# Shruthi-Analog-CS80-SVF-v01_xml.net
KiCad netlist of a schematic drawn in EAGLE
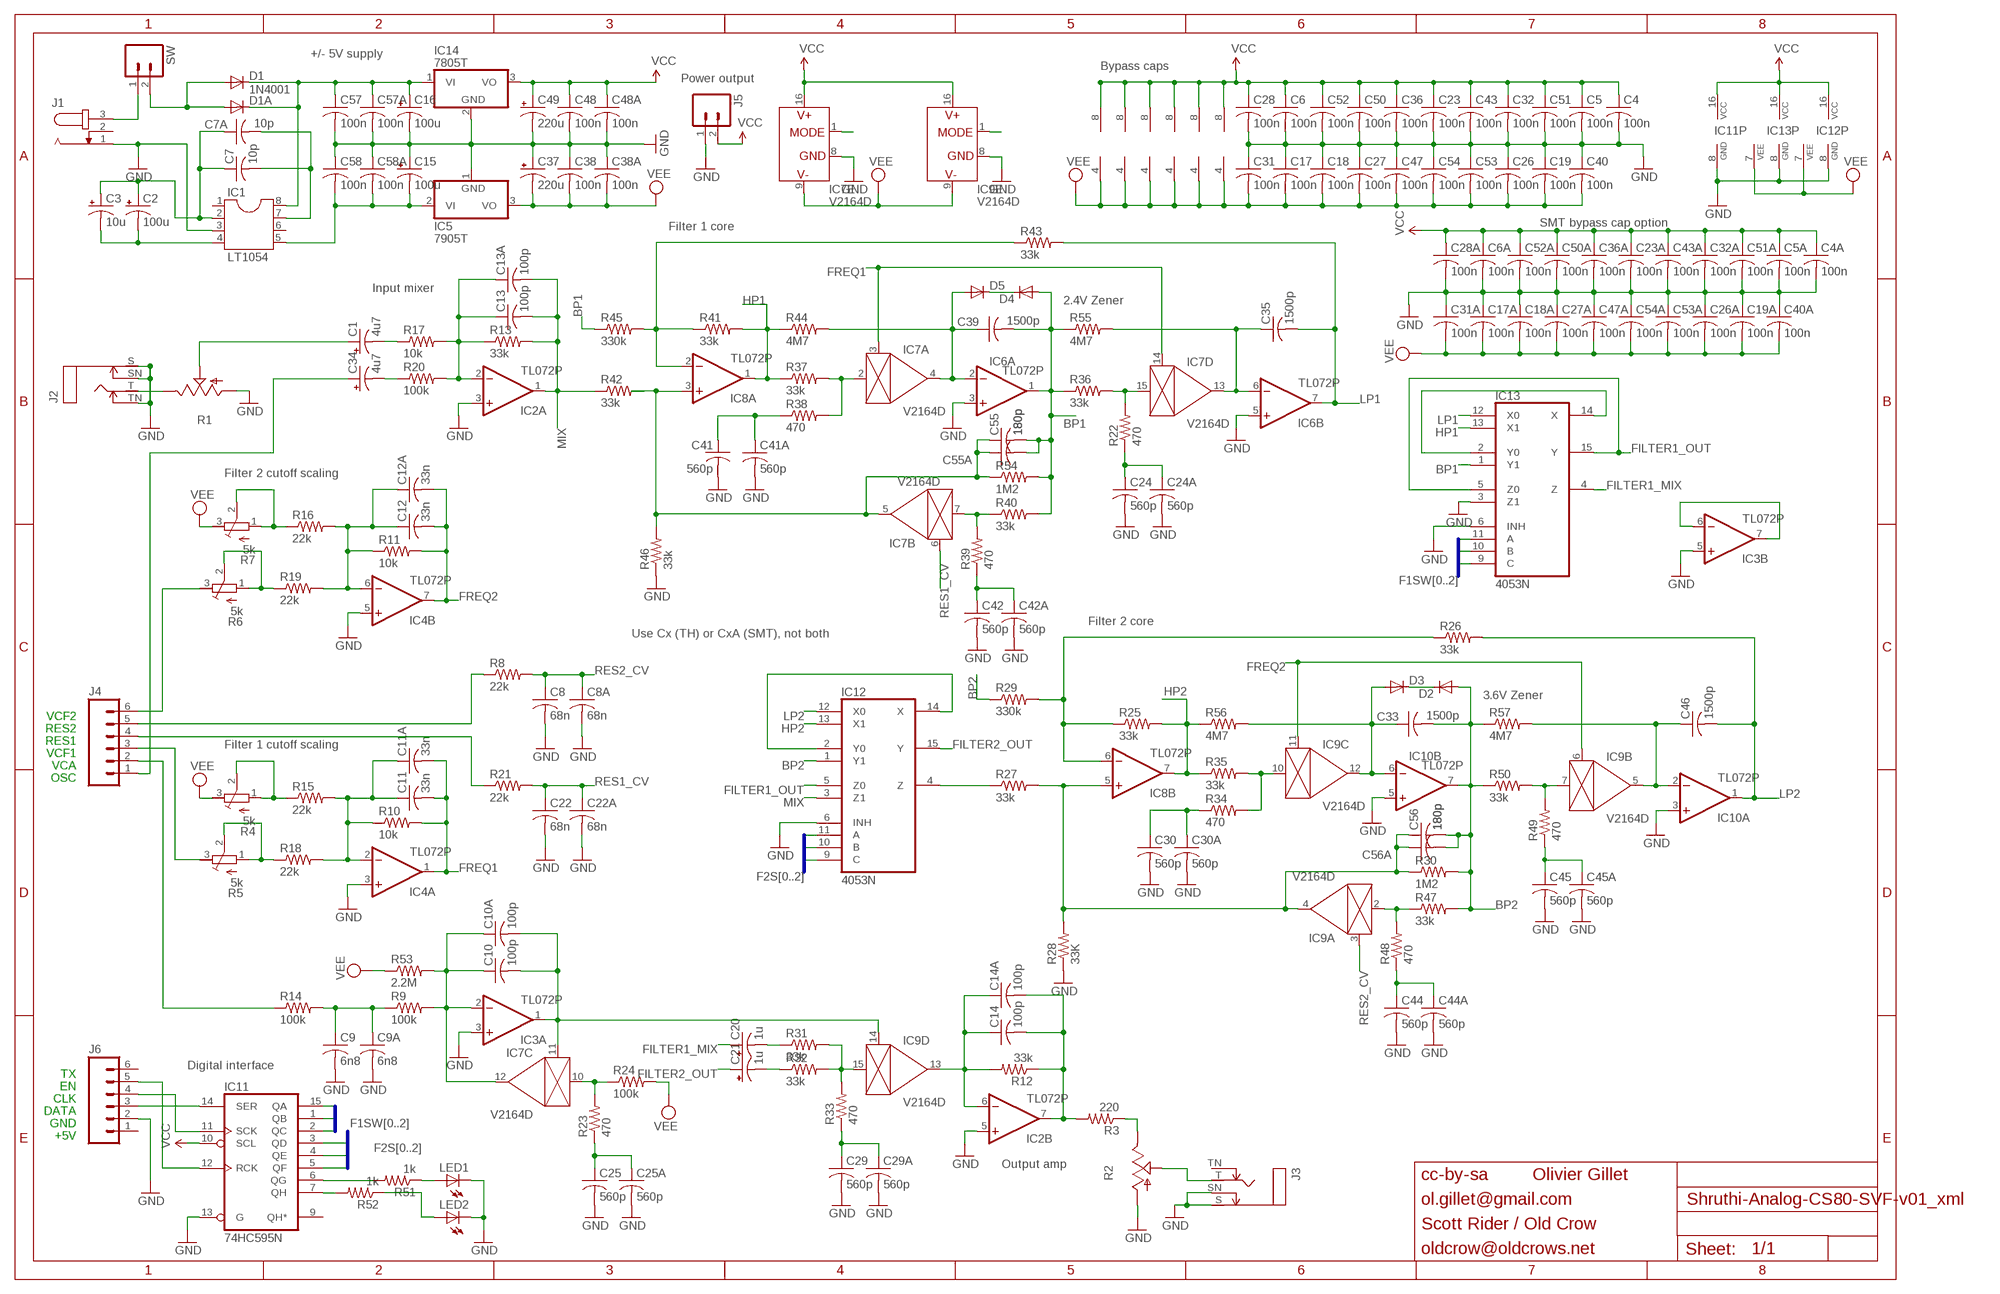
[diagram p0: schematic, sheet 1]

(export (version "E")
  (design (tool "Eeschema 10.0.6"))
  (components
    (comp (ref "C1")
      (value "4u7")
      (footprint "eagle-import:E2,5-6")
      (libsource (lib "eagle-import") (part "CPOL-USE2.5-6"))
    )
    (comp (ref "C2")
      (value "100u")
      (footprint "eagle-import:E2,5-6")
      (libsource (lib "eagle-import") (part "CPOL-USE2.5-6"))
    )
    (comp (ref "C3")
      (value "10u")
      (footprint "eagle-import:E2,5-5")
      (libsource (lib "eagle-import") (part "CPOL-USE2.5-5"))
    )
    (comp (ref "C4")
      (value "100n")
      (footprint "eagle-import:C050-025X075")
      (libsource (lib "eagle-import") (part "C-US050-025X075"))
    )
    (comp (ref "C4A")
      (value "100n")
      (footprint "eagle-import:C0805K")
      (libsource (lib "eagle-import") (part "C-USC0805K"))
    )
    (comp (ref "C5")
      (value "100n")
      (footprint "eagle-import:C050-025X075")
      (libsource (lib "eagle-import") (part "C-US050-025X075"))
    )
    (comp (ref "C5A")
      (value "100n")
      (footprint "eagle-import:C0805K")
      (libsource (lib "eagle-import") (part "C-USC0805K"))
    )
    (comp (ref "C6")
      (value "100n")
      (footprint "eagle-import:C050-025X075")
      (libsource (lib "eagle-import") (part "C-US050-025X075"))
    )
    (comp (ref "C6A")
      (value "100n")
      (footprint "eagle-import:C0805K")
      (libsource (lib "eagle-import") (part "C-USC0805K"))
    )
    (comp (ref "C7")
      (value "10p")
      (footprint "eagle-import:C050-025X075")
      (libsource (lib "eagle-import") (part "C-US050-025X075"))
    )
    (comp (ref "C7A")
      (value "10p")
      (footprint "eagle-import:C0805K")
      (libsource (lib "eagle-import") (part "C-USC0805K"))
    )
    (comp (ref "C8")
      (value "68n")
      (footprint "eagle-import:C050-025X075")
      (libsource (lib "eagle-import") (part "C-US050-025X075"))
    )
    (comp (ref "C8A")
      (value "68n")
      (footprint "eagle-import:C0805K")
      (libsource (lib "eagle-import") (part "C-USC0805K"))
    )
    (comp (ref "C9")
      (value "6n8")
      (footprint "eagle-import:C050-025X075")
      (libsource (lib "eagle-import") (part "C-US050-025X075"))
    )
    (comp (ref "C9A")
      (value "6n8")
      (footprint "eagle-import:C0805K")
      (libsource (lib "eagle-import") (part "C-USC0805K"))
    )
    (comp (ref "C10")
      (value "100p")
      (footprint "eagle-import:C050-025X075")
      (libsource (lib "eagle-import") (part "C-US050-025X075"))
    )
    (comp (ref "C10A")
      (value "100p")
      (footprint "eagle-import:C0805K")
      (libsource (lib "eagle-import") (part "C-USC0805K"))
    )
    (comp (ref "C11")
      (value "33n")
      (footprint "eagle-import:C050-025X075")
      (libsource (lib "eagle-import") (part "C-US050-025X075"))
    )
    (comp (ref "C11A")
      (value "33n")
      (footprint "eagle-import:C0805K")
      (libsource (lib "eagle-import") (part "C-USC0805K"))
    )
    (comp (ref "C12")
      (value "33n")
      (footprint "eagle-import:C050-025X075")
      (libsource (lib "eagle-import") (part "C-US050-025X075"))
    )
    (comp (ref "C12A")
      (value "33n")
      (footprint "eagle-import:C0805K")
      (libsource (lib "eagle-import") (part "C-USC0805K"))
    )
    (comp (ref "C13")
      (value "100p")
      (footprint "eagle-import:C050-025X075")
      (libsource (lib "eagle-import") (part "C-US050-025X075"))
    )
    (comp (ref "C13A")
      (value "100p")
      (footprint "eagle-import:C0805K")
      (libsource (lib "eagle-import") (part "C-USC0805K"))
    )
    (comp (ref "C14")
      (value "100p")
      (footprint "eagle-import:C050-025X075")
      (libsource (lib "eagle-import") (part "C-US050-025X075"))
    )
    (comp (ref "C14A")
      (value "100p")
      (footprint "eagle-import:C0805K")
      (libsource (lib "eagle-import") (part "C-USC0805K"))
    )
    (comp (ref "C15")
      (value "100u")
      (footprint "eagle-import:E2,5-7")
      (libsource (lib "eagle-import") (part "CPOL-USE2.5-7"))
    )
    (comp (ref "C16")
      (value "100u")
      (footprint "eagle-import:E2,5-7")
      (libsource (lib "eagle-import") (part "CPOL-USE2.5-7"))
    )
    (comp (ref "C17")
      (value "100n")
      (footprint "eagle-import:C050-025X075")
      (libsource (lib "eagle-import") (part "C-US050-025X075"))
    )
    (comp (ref "C17A")
      (value "100n")
      (footprint "eagle-import:C0805K")
      (libsource (lib "eagle-import") (part "C-USC0805K"))
    )
    (comp (ref "C18")
      (value "100n")
      (footprint "eagle-import:C050-025X075")
      (libsource (lib "eagle-import") (part "C-US050-025X075"))
    )
    (comp (ref "C18A")
      (value "100n")
      (footprint "eagle-import:C0805K")
      (libsource (lib "eagle-import") (part "C-USC0805K"))
    )
    (comp (ref "C19")
      (value "100n")
      (footprint "eagle-import:C050-025X075")
      (libsource (lib "eagle-import") (part "C-US050-025X075"))
    )
    (comp (ref "C19A")
      (value "100n")
      (footprint "eagle-import:C0805K")
      (libsource (lib "eagle-import") (part "C-USC0805K"))
    )
    (comp (ref "C20")
      (value "1u")
      (footprint "eagle-import:E2-5")
      (libsource (lib "eagle-import") (part "CPOL-USE2-5"))
    )
    (comp (ref "C21")
      (value "1u")
      (footprint "eagle-import:E2-5")
      (libsource (lib "eagle-import") (part "CPOL-USE2-5"))
    )
    (comp (ref "C22")
      (value "68n")
      (footprint "eagle-import:C050-025X075")
      (libsource (lib "eagle-import") (part "C-US050-025X075"))
    )
    (comp (ref "C22A")
      (value "68n")
      (footprint "eagle-import:C0805K")
      (libsource (lib "eagle-import") (part "C-USC0805K"))
    )
    (comp (ref "C23")
      (value "100n")
      (footprint "eagle-import:C050-025X075")
      (libsource (lib "eagle-import") (part "C-US050-025X075"))
    )
    (comp (ref "C23A")
      (value "100n")
      (footprint "eagle-import:C0805K")
      (libsource (lib "eagle-import") (part "C-USC0805K"))
    )
    (comp (ref "C24")
      (value "560p")
      (footprint "eagle-import:C050-025X075")
      (libsource (lib "eagle-import") (part "C-US050-025X075"))
    )
    (comp (ref "C24A")
      (value "560p")
      (footprint "eagle-import:C0805K")
      (libsource (lib "eagle-import") (part "C-USC0805K"))
    )
    (comp (ref "C25")
      (value "560p")
      (footprint "eagle-import:C050-025X075")
      (libsource (lib "eagle-import") (part "C-US050-025X075"))
    )
    (comp (ref "C25A")
      (value "560p")
      (footprint "eagle-import:C0805K")
      (libsource (lib "eagle-import") (part "C-USC0805K"))
    )
    (comp (ref "C26")
      (value "100n")
      (footprint "eagle-import:C050-025X075")
      (libsource (lib "eagle-import") (part "C-US050-025X075"))
    )
    (comp (ref "C26A")
      (value "100n")
      (footprint "eagle-import:C0805K")
      (libsource (lib "eagle-import") (part "C-USC0805K"))
    )
    (comp (ref "C27")
      (value "100n")
      (footprint "eagle-import:C050-025X075")
      (libsource (lib "eagle-import") (part "C-US050-025X075"))
    )
    (comp (ref "C27A")
      (value "100n")
      (footprint "eagle-import:C0805K")
      (libsource (lib "eagle-import") (part "C-USC0805K"))
    )
    (comp (ref "C28")
      (value "100n")
      (footprint "eagle-import:C050-025X075")
      (libsource (lib "eagle-import") (part "C-US050-025X075"))
    )
    (comp (ref "C28A")
      (value "100n")
      (footprint "eagle-import:C0805K")
      (libsource (lib "eagle-import") (part "C-USC0805K"))
    )
    (comp (ref "C29")
      (value "560p")
      (footprint "eagle-import:C050-025X075")
      (libsource (lib "eagle-import") (part "C-US050-025X075"))
    )
    (comp (ref "C29A")
      (value "560p")
      (footprint "eagle-import:C0805K")
      (libsource (lib "eagle-import") (part "C-USC0805K"))
    )
    (comp (ref "C30")
      (value "560p")
      (footprint "eagle-import:C050-025X075")
      (libsource (lib "eagle-import") (part "C-US050-025X075"))
    )
    (comp (ref "C30A")
      (value "560p")
      (footprint "eagle-import:C0805K")
      (libsource (lib "eagle-import") (part "C-USC0805K"))
    )
    (comp (ref "C31")
      (value "100n")
      (footprint "eagle-import:C050-025X075")
      (libsource (lib "eagle-import") (part "C-US050-025X075"))
    )
    (comp (ref "C31A")
      (value "100n")
      (footprint "eagle-import:C0805K")
      (libsource (lib "eagle-import") (part "C-USC0805K"))
    )
    (comp (ref "C32")
      (value "100n")
      (footprint "eagle-import:C050-025X075")
      (libsource (lib "eagle-import") (part "C-US050-025X075"))
    )
    (comp (ref "C32A")
      (value "100n")
      (footprint "eagle-import:C0805K")
      (libsource (lib "eagle-import") (part "C-USC0805K"))
    )
    (comp (ref "C33")
      (value "1500p")
      (footprint "eagle-import:C025-025X050")
      (libsource (lib "eagle-import") (part "C-US025-025X050"))
    )
    (comp (ref "C34")
      (value "4u7")
      (footprint "eagle-import:E2,5-6")
      (libsource (lib "eagle-import") (part "CPOL-USE2.5-6"))
    )
    (comp (ref "C35")
      (value "1500p")
      (footprint "eagle-import:C025-025X050")
      (libsource (lib "eagle-import") (part "C-US025-025X050"))
    )
    (comp (ref "C36")
      (value "100n")
      (footprint "eagle-import:C050-025X075")
      (libsource (lib "eagle-import") (part "C-US050-025X075"))
    )
    (comp (ref "C36A")
      (value "100n")
      (footprint "eagle-import:C0805K")
      (libsource (lib "eagle-import") (part "C-USC0805K"))
    )
    (comp (ref "C37")
      (value "220u")
      (footprint "eagle-import:E3,5-8")
      (libsource (lib "eagle-import") (part "CPOL-USE3.5-8"))
    )
    (comp (ref "C38")
      (value "100n")
      (footprint "eagle-import:C050-025X075")
      (libsource (lib "eagle-import") (part "C-US050-025X075"))
    )
    (comp (ref "C38A")
      (value "100n")
      (footprint "eagle-import:C0805K")
      (libsource (lib "eagle-import") (part "C-USC0805K"))
    )
    (comp (ref "C39")
      (value "1500p")
      (footprint "eagle-import:C025-025X050")
      (libsource (lib "eagle-import") (part "C-US025-025X050"))
    )
    (comp (ref "C40")
      (value "100n")
      (footprint "eagle-import:C050-025X075")
      (libsource (lib "eagle-import") (part "C-US050-025X075"))
    )
    (comp (ref "C40A")
      (value "100n")
      (footprint "eagle-import:C0805K")
      (libsource (lib "eagle-import") (part "C-USC0805K"))
    )
    (comp (ref "C41")
      (value "560p")
      (footprint "eagle-import:C050-025X075")
      (libsource (lib "eagle-import") (part "C-US050-025X075"))
    )
    (comp (ref "C41A")
      (value "560p")
      (footprint "eagle-import:C0805K")
      (libsource (lib "eagle-import") (part "C-USC0805K"))
    )
    (comp (ref "C42")
      (value "560p")
      (footprint "eagle-import:C050-025X075")
      (libsource (lib "eagle-import") (part "C-US050-025X075"))
    )
    (comp (ref "C42A")
      (value "560p")
      (footprint "eagle-import:C0805K")
      (libsource (lib "eagle-import") (part "C-USC0805K"))
    )
    (comp (ref "C43")
      (value "100n")
      (footprint "eagle-import:C050-025X075")
      (libsource (lib "eagle-import") (part "C-US050-025X075"))
    )
    (comp (ref "C43A")
      (value "100n")
      (footprint "eagle-import:C0805K")
      (libsource (lib "eagle-import") (part "C-USC0805K"))
    )
    (comp (ref "C44")
      (value "560p")
      (footprint "eagle-import:C050-025X075")
      (libsource (lib "eagle-import") (part "C-US050-025X075"))
    )
    (comp (ref "C44A")
      (value "560p")
      (footprint "eagle-import:C0805K")
      (libsource (lib "eagle-import") (part "C-USC0805K"))
    )
    (comp (ref "C45")
      (value "560p")
      (footprint "eagle-import:C050-025X075")
      (libsource (lib "eagle-import") (part "C-US050-025X075"))
    )
    (comp (ref "C45A")
      (value "560p")
      (footprint "eagle-import:C0805K")
      (libsource (lib "eagle-import") (part "C-USC0805K"))
    )
    (comp (ref "C46")
      (value "1500p")
      (footprint "eagle-import:C025-025X050")
      (libsource (lib "eagle-import") (part "C-US025-025X050"))
    )
    (comp (ref "C47")
      (value "100n")
      (footprint "eagle-import:C050-025X075")
      (libsource (lib "eagle-import") (part "C-US050-025X075"))
    )
    (comp (ref "C47A")
      (value "100n")
      (footprint "eagle-import:C0805K")
      (libsource (lib "eagle-import") (part "C-USC0805K"))
    )
    (comp (ref "C48")
      (value "100n")
      (footprint "eagle-import:C050-025X075")
      (libsource (lib "eagle-import") (part "C-US050-025X075"))
    )
    (comp (ref "C48A")
      (value "100n")
      (footprint "eagle-import:C0805K")
      (libsource (lib "eagle-import") (part "C-USC0805K"))
    )
    (comp (ref "C49")
      (value "220u")
      (footprint "eagle-import:E3,5-8")
      (libsource (lib "eagle-import") (part "CPOL-USE3.5-8"))
    )
    (comp (ref "C50")
      (value "100n")
      (footprint "eagle-import:C050-025X075")
      (libsource (lib "eagle-import") (part "C-US050-025X075"))
    )
    (comp (ref "C50A")
      (value "100n")
      (footprint "eagle-import:C0805K")
      (libsource (lib "eagle-import") (part "C-USC0805K"))
    )
    (comp (ref "C51")
      (value "100n")
      (footprint "eagle-import:C050-025X075")
      (libsource (lib "eagle-import") (part "C-US050-025X075"))
    )
    (comp (ref "C51A")
      (value "100n")
      (footprint "eagle-import:C0805K")
      (libsource (lib "eagle-import") (part "C-USC0805K"))
    )
    (comp (ref "C52")
      (value "100n")
      (footprint "eagle-import:C050-025X075")
      (libsource (lib "eagle-import") (part "C-US050-025X075"))
    )
    (comp (ref "C52A")
      (value "100n")
      (footprint "eagle-import:C0805K")
      (libsource (lib "eagle-import") (part "C-USC0805K"))
    )
    (comp (ref "C53")
      (value "100n")
      (footprint "eagle-import:C025-025X050")
      (libsource (lib "eagle-import") (part "C-US025-025X050"))
    )
    (comp (ref "C53A")
      (value "100n")
      (footprint "eagle-import:C0805K")
      (libsource (lib "eagle-import") (part "C-USC0805K"))
    )
    (comp (ref "C54")
      (value "100n")
      (footprint "eagle-import:C050-025X075")
      (libsource (lib "eagle-import") (part "C-US050-025X075"))
    )
    (comp (ref "C54A")
      (value "100n")
      (footprint "eagle-import:C0805K")
      (libsource (lib "eagle-import") (part "C-USC0805K"))
    )
    (comp (ref "C55")
      (value "180p")
      (footprint "eagle-import:C050-025X075")
      (libsource (lib "eagle-import") (part "C-US050-025X075"))
    )
    (comp (ref "C55A")
      (value "180p")
      (footprint "eagle-import:C0805K")
      (libsource (lib "eagle-import") (part "C-USC0805K"))
    )
    (comp (ref "C56")
      (value "180p")
      (footprint "eagle-import:C050-025X075")
      (libsource (lib "eagle-import") (part "C-US050-025X075"))
    )
    (comp (ref "C56A")
      (value "180p")
      (footprint "eagle-import:C0805K")
      (libsource (lib "eagle-import") (part "C-USC0805K"))
    )
    (comp (ref "C57")
      (value "100n")
      (footprint "eagle-import:C050-025X075")
      (libsource (lib "eagle-import") (part "C-US050-025X075"))
    )
    (comp (ref "C57A")
      (value "100n")
      (footprint "eagle-import:C0805K")
      (libsource (lib "eagle-import") (part "C-USC0805K"))
    )
    (comp (ref "C58")
      (value "100n")
      (footprint "eagle-import:C050-025X075")
      (libsource (lib "eagle-import") (part "C-US050-025X075"))
    )
    (comp (ref "C58A")
      (value "100n")
      (footprint "eagle-import:C0805K")
      (libsource (lib "eagle-import") (part "C-USC0805K"))
    )
    (comp (ref "D1")
      (value "1N4001")
      (footprint "eagle-import:DO41-10")
      (libsource (lib "eagle-import") (part "1N4004"))
    )
    (comp (ref "D1A")
      (value "DIODE-SMB")
      (footprint "eagle-import:SMB")
      (libsource (lib "eagle-import") (part "DIODE-SMB"))
    )
    (comp (ref "D2")
      (value "DIODE-D-5")
      (footprint "eagle-import:D-5")
      (libsource (lib "eagle-import") (part "DIODE-D-5"))
    )
    (comp (ref "D3")
      (value "DIODE-D-5")
      (footprint "eagle-import:D-5")
      (libsource (lib "eagle-import") (part "DIODE-D-5"))
    )
    (comp (ref "D4")
      (value "DIODE-D-5")
      (footprint "eagle-import:D-5")
      (libsource (lib "eagle-import") (part "DIODE-D-5"))
    )
    (comp (ref "D5")
      (value "DIODE-D-5")
      (footprint "eagle-import:D-5")
      (libsource (lib "eagle-import") (part "DIODE-D-5"))
    )
    (comp (ref "IC1")
      (value "LT1054")
      (footprint "eagle-import:DIL08")
      (libsource (lib "eagle-import") (part "DIL8"))
    )
    (comp (ref "IC2")
      (value "TL072P")
      (footprint "eagle-import:DIL08")
      (libsource (lib "eagle-import") (part "TL072P"))
    )
    (comp (ref "IC3")
      (value "TL072P")
      (footprint "eagle-import:DIL08")
      (libsource (lib "eagle-import") (part "TL072P"))
    )
    (comp (ref "IC4")
      (value "TL072P")
      (footprint "eagle-import:DIL08")
      (libsource (lib "eagle-import") (part "TL072P"))
    )
    (comp (ref "IC5")
      (value "7905T")
      (footprint "eagle-import:TO220H")
      (libsource (lib "eagle-import") (part "79T05"))
    )
    (comp (ref "IC6")
      (value "TL072P")
      (footprint "eagle-import:DIL08")
      (libsource (lib "eagle-import") (part "TL072P"))
    )
    (comp (ref "IC7")
      (value "V2164D")
      (footprint "eagle-import:DIL16")
      (libsource (lib "eagle-import") (part "SSM2164P"))
    )
    (comp (ref "IC8")
      (value "TL072P")
      (footprint "eagle-import:DIL08")
      (libsource (lib "eagle-import") (part "TL072P"))
    )
    (comp (ref "IC9")
      (value "V2164D")
      (footprint "eagle-import:DIL16")
      (libsource (lib "eagle-import") (part "SSM2164P"))
    )
    (comp (ref "IC10")
      (value "TL072P")
      (footprint "eagle-import:DIL08")
      (libsource (lib "eagle-import") (part "TL072P"))
    )
    (comp (ref "IC11")
      (value "74HC595N")
      (footprint "eagle-import:DIL16")
      (libsource (lib "eagle-import") (part "74595NHC"))
    )
    (comp (ref "IC12")
      (value "4053N")
      (footprint "eagle-import:DIL16")
      (libsource (lib "eagle-import") (part "4053N"))
    )
    (comp (ref "IC13")
      (value "4053N")
      (footprint "eagle-import:DIL16")
      (libsource (lib "eagle-import") (part "4053N"))
    )
    (comp (ref "IC14")
      (value "7805T")
      (footprint "eagle-import:TO220H")
      (libsource (lib "eagle-import") (part "78T05"))
    )
    (comp (ref "J1")
      (value "JACK-PLUG2")
      (footprint "eagle-import:SPC4078_BIG_HOLES")
      (libsource (lib "eagle-import") (part "JACK-PLUG2"))
    )
    (comp (ref "J2")
      (value "MONOSWS")
      (footprint "eagle-import:NMJ4HC-S")
      (libsource (lib "eagle-import") (part "MONOSWS"))
    )
    (comp (ref "J3")
      (value "MONOSWS")
      (footprint "eagle-import:NMJ4HC-S")
      (libsource (lib "eagle-import") (part "MONOSWS"))
    )
    (comp (ref "J4")
      (value "M06SIP")
      (footprint "eagle-import:1X06")
      (libsource (lib "eagle-import") (part "M06SIP"))
    )
    (comp (ref "J5")
      (value "M02PTH")
      (footprint "eagle-import:1X02")
      (libsource (lib "eagle-import") (part "M02PTH"))
    )
    (comp (ref "J6")
      (value "M06SIP")
      (footprint "eagle-import:1X06")
      (libsource (lib "eagle-import") (part "M06SIP"))
    )
    (comp (ref "LED1")
      (value "LEDCHIP-LED0603")
      (footprint "eagle-import:CHIP-LED0603")
      (libsource (lib "eagle-import") (part "LEDCHIP-LED0603"))
    )
    (comp (ref "LED2")
      (value "LEDCHIP-LED0603")
      (footprint "eagle-import:CHIP-LED0603")
      (libsource (lib "eagle-import") (part "LEDCHIP-LED0603"))
    )
    (comp (ref "R1")
      (value "POT_USCABLED")
      (footprint "eagle-import:CABLE_POT_6MM")
      (libsource (lib "eagle-import") (part "POT_USCABLED"))
    )
    (comp (ref "R2")
      (value "POT_USCABLED")
      (footprint "eagle-import:CABLE_POT_6MM")
      (libsource (lib "eagle-import") (part "POT_USCABLED"))
    )
    (comp (ref "R3")
      (value "220")
      (footprint "eagle-import:0204_7")
      (libsource (lib "eagle-import") (part "R-US_0204/7"))
    )
    (comp (ref "R4")
      (value "5k")
      (footprint "eagle-import:RTRIM3296X")
      (libsource (lib "eagle-import") (part "R-TRIMM3296X"))
    )
    (comp (ref "R5")
      (value "5k")
      (footprint "eagle-import:RTRIM3296X")
      (libsource (lib "eagle-import") (part "R-TRIMM3296X"))
    )
    (comp (ref "R6")
      (value "5k")
      (footprint "eagle-import:RTRIM3296X")
      (libsource (lib "eagle-import") (part "R-TRIMM3296X"))
    )
    (comp (ref "R7")
      (value "5k")
      (footprint "eagle-import:RTRIM3296X")
      (libsource (lib "eagle-import") (part "R-TRIMM3296X"))
    )
    (comp (ref "R8")
      (value "22k")
      (footprint "eagle-import:0204_7")
      (libsource (lib "eagle-import") (part "R-US_0204/7"))
    )
    (comp (ref "R9")
      (value "100k")
      (footprint "eagle-import:0204_7")
      (libsource (lib "eagle-import") (part "R-US_0204/7"))
    )
    (comp (ref "R10")
      (value "10k")
      (footprint "eagle-import:0204_7")
      (libsource (lib "eagle-import") (part "R-US_0204/7"))
    )
    (comp (ref "R11")
      (value "10k")
      (footprint "eagle-import:0204_7")
      (libsource (lib "eagle-import") (part "R-US_0204/7"))
    )
    (comp (ref "R12")
      (value "33k")
      (footprint "eagle-import:0204_7")
      (libsource (lib "eagle-import") (part "R-US_0204/7"))
    )
    (comp (ref "R13")
      (value "33k")
      (footprint "eagle-import:0204_7")
      (libsource (lib "eagle-import") (part "R-US_0204/7"))
    )
    (comp (ref "R14")
      (value "100k")
      (footprint "eagle-import:0204_7")
      (libsource (lib "eagle-import") (part "R-US_0204/7"))
    )
    (comp (ref "R15")
      (value "22k")
      (footprint "eagle-import:0204_7")
      (libsource (lib "eagle-import") (part "R-US_0204/7"))
    )
    (comp (ref "R16")
      (value "22k")
      (footprint "eagle-import:0204_7")
      (libsource (lib "eagle-import") (part "R-US_0204/7"))
    )
    (comp (ref "R17")
      (value "10k")
      (footprint "eagle-import:0204_7")
      (libsource (lib "eagle-import") (part "R-US_0204/7"))
    )
    (comp (ref "R18")
      (value "22k")
      (footprint "eagle-import:0204_7")
      (libsource (lib "eagle-import") (part "R-US_0204/7"))
    )
    (comp (ref "R19")
      (value "22k")
      (footprint "eagle-import:0204_7")
      (libsource (lib "eagle-import") (part "R-US_0204/7"))
    )
    (comp (ref "R20")
      (value "100k")
      (footprint "eagle-import:0204_7")
      (libsource (lib "eagle-import") (part "R-US_0204/7"))
    )
    (comp (ref "R21")
      (value "22k")
      (footprint "eagle-import:0204_7")
      (libsource (lib "eagle-import") (part "R-US_0204/7"))
    )
    (comp (ref "R22")
      (value "470")
      (footprint "eagle-import:0204_7")
      (libsource (lib "eagle-import") (part "R-US_0204/7"))
    )
    (comp (ref "R23")
      (value "470")
      (footprint "eagle-import:0204_7")
      (libsource (lib "eagle-import") (part "R-US_0204/7"))
    )
    (comp (ref "R24")
      (value "100k")
      (footprint "eagle-import:0204_7")
      (libsource (lib "eagle-import") (part "R-US_0204/7"))
    )
    (comp (ref "R25")
      (value "33k")
      (footprint "eagle-import:0204_7")
      (libsource (lib "eagle-import") (part "R-US_0204/7"))
    )
    (comp (ref "R26")
      (value "33k")
      (footprint "eagle-import:0204_7")
      (libsource (lib "eagle-import") (part "R-US_0204/7"))
    )
    (comp (ref "R27")
      (value "33k")
      (footprint "eagle-import:0204_7")
      (libsource (lib "eagle-import") (part "R-US_0204/7"))
    )
    (comp (ref "R28")
      (value "33K")
      (footprint "eagle-import:0204_7")
      (libsource (lib "eagle-import") (part "R-US_0204/7"))
    )
    (comp (ref "R29")
      (value "330k")
      (footprint "eagle-import:0204_7")
      (libsource (lib "eagle-import") (part "R-US_0204/7"))
    )
    (comp (ref "R30")
      (value "1M2")
      (footprint "eagle-import:0204_7")
      (libsource (lib "eagle-import") (part "R-US_0204/7"))
    )
    (comp (ref "R31")
      (value "33k")
      (footprint "eagle-import:0204_7")
      (libsource (lib "eagle-import") (part "R-US_0204/7"))
    )
    (comp (ref "R32")
      (value "33k")
      (footprint "eagle-import:0204_7")
      (libsource (lib "eagle-import") (part "R-US_0204/7"))
    )
    (comp (ref "R33")
      (value "470")
      (footprint "eagle-import:0204_7")
      (libsource (lib "eagle-import") (part "R-US_0204/7"))
    )
    (comp (ref "R34")
      (value "470")
      (footprint "eagle-import:0204_7")
      (libsource (lib "eagle-import") (part "R-US_0204/7"))
    )
    (comp (ref "R35")
      (value "33k")
      (footprint "eagle-import:0204_7")
      (libsource (lib "eagle-import") (part "R-US_0204/7"))
    )
    (comp (ref "R36")
      (value "33k")
      (footprint "eagle-import:0204_7")
      (libsource (lib "eagle-import") (part "R-US_0204/7"))
    )
    (comp (ref "R37")
      (value "33k")
      (footprint "eagle-import:0204_7")
      (libsource (lib "eagle-import") (part "R-US_0204/7"))
    )
    (comp (ref "R38")
      (value "470")
      (footprint "eagle-import:0204_7")
      (libsource (lib "eagle-import") (part "R-US_0204/7"))
    )
    (comp (ref "R39")
      (value "470")
      (footprint "eagle-import:0204_7")
      (libsource (lib "eagle-import") (part "R-US_0204/7"))
    )
    (comp (ref "R40")
      (value "33k")
      (footprint "eagle-import:0204_7")
      (libsource (lib "eagle-import") (part "R-US_0204/7"))
    )
    (comp (ref "R41")
      (value "33k")
      (footprint "eagle-import:0204_7")
      (libsource (lib "eagle-import") (part "R-US_0204/7"))
    )
    (comp (ref "R42")
      (value "33k")
      (footprint "eagle-import:0204_7")
      (libsource (lib "eagle-import") (part "R-US_0204/7"))
    )
    (comp (ref "R43")
      (value "33k")
      (footprint "eagle-import:0204_7")
      (libsource (lib "eagle-import") (part "R-US_0204/7"))
    )
    (comp (ref "R44")
      (value "4M7")
      (footprint "eagle-import:0204_7")
      (libsource (lib "eagle-import") (part "R-US_0204/7"))
    )
    (comp (ref "R45")
      (value "330k")
      (footprint "eagle-import:0204_7")
      (libsource (lib "eagle-import") (part "R-US_0204/7"))
    )
    (comp (ref "R46")
      (value "33k")
      (footprint "eagle-import:0204_7")
      (libsource (lib "eagle-import") (part "R-US_0204/7"))
    )
    (comp (ref "R47")
      (value "33k")
      (footprint "eagle-import:0204_7")
      (libsource (lib "eagle-import") (part "R-US_0204/7"))
    )
    (comp (ref "R48")
      (value "470")
      (footprint "eagle-import:0204_7")
      (libsource (lib "eagle-import") (part "R-US_0204/7"))
    )
    (comp (ref "R49")
      (value "470")
      (footprint "eagle-import:0204_7")
      (libsource (lib "eagle-import") (part "R-US_0204/7"))
    )
    (comp (ref "R50")
      (value "33k")
      (footprint "eagle-import:0204_7")
      (libsource (lib "eagle-import") (part "R-US_0204/7"))
    )
    (comp (ref "R51")
      (value "1k")
      (footprint "eagle-import:0204_7")
      (libsource (lib "eagle-import") (part "R-US_0204/7"))
    )
    (comp (ref "R52")
      (value "1k")
      (footprint "eagle-import:0204_7")
      (libsource (lib "eagle-import") (part "R-US_0204/7"))
    )
    (comp (ref "R53")
      (value "2.2M")
      (footprint "eagle-import:0204V")
      (libsource (lib "eagle-import") (part "R-US_0204/2V"))
    )
    (comp (ref "R54")
      (value "1M2")
      (footprint "eagle-import:0204_7")
      (libsource (lib "eagle-import") (part "R-US_0204/7"))
    )
    (comp (ref "R55")
      (value "4M7")
      (footprint "eagle-import:0204_7")
      (libsource (lib "eagle-import") (part "R-US_0204/7"))
    )
    (comp (ref "R56")
      (value "4M7")
      (footprint "eagle-import:0204_7")
      (libsource (lib "eagle-import") (part "R-US_0204/7"))
    )
    (comp (ref "R57")
      (value "4M7")
      (footprint "eagle-import:0204_7")
      (libsource (lib "eagle-import") (part "R-US_0204/7"))
    )
    (comp (ref "SW")
      (value "M02PTH")
      (footprint "eagle-import:1X02")
      (libsource (lib "eagle-import") (part "M02PTH"))
    )
  )
  (nets
    (net (code "4") (name "/BP1") (class "Default")
      (node (ref "C39") (pin "2") (pinfunction "2_2") (pintype "passive"))
      (node (ref "C55") (pin "2") (pinfunction "2_2") (pintype "passive"))
      (node (ref "C55A") (pin "2") (pinfunction "2_2") (pintype "passive"))
      (node (ref "D4") (pin "A") (pinfunction "A_A") (pintype "passive"))
      (node (ref "IC13") (pin "1") (pinfunction "Y1_1") (pintype "bidirectional"))
      (node (ref "IC6") (pin "1") (pinfunction "OUT_1") (pintype "output"))
      (node (ref "R36") (pin "1") (pinfunction "1_1") (pintype "passive"))
      (node (ref "R40") (pin "2") (pinfunction "2_2") (pintype "passive"))
      (node (ref "R45") (pin "1") (pinfunction "1_1") (pintype "passive"))
      (node (ref "R54") (pin "2") (pinfunction "2_2") (pintype "passive"))
      (node (ref "R55") (pin "1") (pinfunction "1_1") (pintype "passive"))
    )
    (net (code "5") (name "/BP2") (class "Default")
      (node (ref "C33") (pin "2") (pinfunction "2_2") (pintype "passive"))
      (node (ref "C56") (pin "2") (pinfunction "2_2") (pintype "passive"))
      (node (ref "C56A") (pin "2") (pinfunction "2_2") (pintype "passive"))
      (node (ref "D2") (pin "A") (pinfunction "A_A") (pintype "passive"))
      (node (ref "IC10") (pin "7") (pinfunction "OUT_7") (pintype "output"))
      (node (ref "IC12") (pin "1") (pinfunction "Y1_1") (pintype "bidirectional"))
      (node (ref "R29") (pin "1") (pinfunction "1_1") (pintype "passive"))
      (node (ref "R30") (pin "2") (pinfunction "2_2") (pintype "passive"))
      (node (ref "R47") (pin "2") (pinfunction "2_2") (pintype "passive"))
      (node (ref "R50") (pin "1") (pinfunction "1_1") (pintype "passive"))
      (node (ref "R57") (pin "1") (pinfunction "1_1") (pintype "passive"))
    )
    (net (code "6") (name "/F1SW0") (class "Default")
      (node (ref "IC11") (pin "15") (pinfunction "QA_15") (pintype "tri_state"))
      (node (ref "IC13") (pin "9") (pinfunction "C_9") (pintype "input"))
    )
    (net (code "7") (name "/F1SW1") (class "Default")
      (node (ref "IC11") (pin "1") (pinfunction "QB_1") (pintype "tri_state"))
      (node (ref "IC13") (pin "10") (pinfunction "B_10") (pintype "input"))
    )
    (net (code "8") (name "/F1SW2") (class "Default")
      (node (ref "IC11") (pin "2") (pinfunction "QC_2") (pintype "tri_state"))
      (node (ref "IC13") (pin "11") (pinfunction "A_11") (pintype "input"))
    )
    (net (code "10") (name "/F2SW0") (class "Default")
      (node (ref "IC11") (pin "3") (pinfunction "QD_3") (pintype "tri_state"))
      (node (ref "IC12") (pin "9") (pinfunction "C_9") (pintype "input"))
    )
    (net (code "11") (name "/F2SW1") (class "Default")
      (node (ref "IC11") (pin "4") (pinfunction "QE_4") (pintype "tri_state"))
      (node (ref "IC12") (pin "10") (pinfunction "B_10") (pintype "input"))
    )
    (net (code "12") (name "/F2SW2") (class "Default")
      (node (ref "IC11") (pin "5") (pinfunction "QF_5") (pintype "tri_state"))
      (node (ref "IC12") (pin "11") (pinfunction "A_11") (pintype "input"))
    )
    (net (code "14") (name "/FILTER1_MIX") (class "Default")
      (node (ref "C20") (pin "+") (pinfunction "+_+") (pintype "passive"))
      (node (ref "IC13") (pin "4") (pinfunction "Z_4") (pintype "bidirectional"))
    )
    (net (code "15") (name "/FILTER1_OUT") (class "Default")
      (node (ref "IC12") (pin "5") (pinfunction "Z0_5") (pintype "bidirectional"))
      (node (ref "IC13") (pin "15") (pinfunction "Y_15") (pintype "bidirectional"))
      (node (ref "IC13") (pin "5") (pinfunction "Z0_5") (pintype "bidirectional"))
    )
    (net (code "16") (name "/FILTER2_OUT") (class "Default")
      (node (ref "C21") (pin "+") (pinfunction "+_+") (pintype "passive"))
      (node (ref "IC12") (pin "15") (pinfunction "Y_15") (pintype "bidirectional"))
    )
    (net (code "17") (name "/FREQ1") (class "Default")
      (node (ref "C11") (pin "2") (pinfunction "2_2") (pintype "passive"))
      (node (ref "C11A") (pin "2") (pinfunction "2_2") (pintype "passive"))
      (node (ref "IC4") (pin "1") (pinfunction "OUT_1") (pintype "output"))
      (node (ref "IC7") (pin "14") (pinfunction "CTRL_14") (pintype "input"))
      (node (ref "IC7") (pin "3") (pinfunction "CTRL_3") (pintype "input"))
      (node (ref "R10") (pin "2") (pinfunction "2_2") (pintype "passive"))
    )
    (net (code "18") (name "/FREQ2") (class "Default")
      (node (ref "C12") (pin "2") (pinfunction "2_2") (pintype "passive"))
      (node (ref "C12A") (pin "2") (pinfunction "2_2") (pintype "passive"))
      (node (ref "IC4") (pin "7") (pinfunction "OUT_7") (pintype "output"))
      (node (ref "IC9") (pin "11") (pinfunction "CTRL_11") (pintype "input"))
      (node (ref "IC9") (pin "6") (pinfunction "CTRL_6") (pintype "input"))
      (node (ref "R11") (pin "2") (pinfunction "2_2") (pintype "passive"))
    )
    (net (code "19") (name "/HP1") (class "Default")
      (node (ref "IC13") (pin "13") (pinfunction "X1_13") (pintype "bidirectional"))
      (node (ref "IC8") (pin "1") (pinfunction "OUT_1") (pintype "output"))
      (node (ref "R37") (pin "1") (pinfunction "1_1") (pintype "passive"))
      (node (ref "R41") (pin "2") (pinfunction "2_2") (pintype "passive"))
      (node (ref "R44") (pin "1") (pinfunction "1_1") (pintype "passive"))
    )
    (net (code "20") (name "/HP2") (class "Default")
      (node (ref "IC12") (pin "13") (pinfunction "X1_13") (pintype "bidirectional"))
      (node (ref "IC8") (pin "7") (pinfunction "OUT_7") (pintype "output"))
      (node (ref "R25") (pin "2") (pinfunction "2_2") (pintype "passive"))
      (node (ref "R35") (pin "1") (pinfunction "1_1") (pintype "passive"))
      (node (ref "R56") (pin "1") (pinfunction "1_1") (pintype "passive"))
    )
    (net (code "21") (name "/LP1") (class "Default")
      (node (ref "C35") (pin "2") (pinfunction "2_2") (pintype "passive"))
      (node (ref "IC13") (pin "12") (pinfunction "X0_12") (pintype "bidirectional"))
      (node (ref "IC6") (pin "7") (pinfunction "OUT_7") (pintype "output"))
      (node (ref "R43") (pin "2") (pinfunction "2_2") (pintype "passive"))
    )
    (net (code "22") (name "/LP2") (class "Default")
      (node (ref "C46") (pin "2") (pinfunction "2_2") (pintype "passive"))
      (node (ref "IC10") (pin "1") (pinfunction "OUT_1") (pintype "output"))
      (node (ref "IC12") (pin "12") (pinfunction "X0_12") (pintype "bidirectional"))
      (node (ref "R26") (pin "2") (pinfunction "2_2") (pintype "passive"))
    )
    (net (code "23") (name "/MIX") (class "Default")
      (node (ref "C13") (pin "2") (pinfunction "2_2") (pintype "passive"))
      (node (ref "C13A") (pin "2") (pinfunction "2_2") (pintype "passive"))
      (node (ref "IC12") (pin "3") (pinfunction "Z1_3") (pintype "bidirectional"))
      (node (ref "IC2") (pin "1") (pinfunction "OUT_1") (pintype "output"))
      (node (ref "R13") (pin "2") (pinfunction "2_2") (pintype "passive"))
      (node (ref "R42") (pin "1") (pinfunction "1_1") (pintype "passive"))
    )
    (net (code "24") (name "/RES1_CV") (class "Default")
      (node (ref "C22") (pin "1") (pinfunction "1_1") (pintype "passive"))
      (node (ref "C22A") (pin "1") (pinfunction "1_1") (pintype "passive"))
      (node (ref "IC7") (pin "6") (pinfunction "CTRL_6") (pintype "input"))
      (node (ref "R21") (pin "2") (pinfunction "2_2") (pintype "passive"))
    )
    (net (code "25") (name "/RES2_CV") (class "Default")
      (node (ref "C8") (pin "1") (pinfunction "1_1") (pintype "passive"))
      (node (ref "C8A") (pin "1") (pinfunction "1_1") (pintype "passive"))
      (node (ref "IC9") (pin "3") (pinfunction "CTRL_3") (pintype "input"))
      (node (ref "R8") (pin "2") (pinfunction "2_2") (pintype "passive"))
    )
    (net (code "26") (name "GND") (class "Default")
      (node (ref "C15") (pin "+") (pinfunction "+_+") (pintype "passive"))
      (node (ref "C16") (pin "-") (pinfunction "-_-") (pintype "passive"))
      (node (ref "C17") (pin "1") (pinfunction "1_1") (pintype "passive"))
      (node (ref "C17A") (pin "1") (pinfunction "1_1") (pintype "passive"))
      (node (ref "C18") (pin "1") (pinfunction "1_1") (pintype "passive"))
      (node (ref "C18A") (pin "1") (pinfunction "1_1") (pintype "passive"))
      (node (ref "C19") (pin "1") (pinfunction "1_1") (pintype "passive"))
      (node (ref "C19A") (pin "1") (pinfunction "1_1") (pintype "passive"))
      (node (ref "C22") (pin "2") (pinfunction "2_2") (pintype "passive"))
      (node (ref "C22A") (pin "2") (pinfunction "2_2") (pintype "passive"))
      (node (ref "C23") (pin "2") (pinfunction "2_2") (pintype "passive"))
      (node (ref "C23A") (pin "2") (pinfunction "2_2") (pintype "passive"))
      (node (ref "C24") (pin "2") (pinfunction "2_2") (pintype "passive"))
      (node (ref "C24A") (pin "2") (pinfunction "2_2") (pintype "passive"))
      (node (ref "C25") (pin "2") (pinfunction "2_2") (pintype "passive"))
      (node (ref "C25A") (pin "2") (pinfunction "2_2") (pintype "passive"))
      (node (ref "C26") (pin "1") (pinfunction "1_1") (pintype "passive"))
      (node (ref "C26A") (pin "1") (pinfunction "1_1") (pintype "passive"))
      (node (ref "C27") (pin "1") (pinfunction "1_1") (pintype "passive"))
      (node (ref "C27A") (pin "1") (pinfunction "1_1") (pintype "passive"))
      (node (ref "C28") (pin "2") (pinfunction "2_2") (pintype "passive"))
      (node (ref "C28A") (pin "2") (pinfunction "2_2") (pintype "passive"))
      (node (ref "C29") (pin "2") (pinfunction "2_2") (pintype "passive"))
      (node (ref "C29A") (pin "2") (pinfunction "2_2") (pintype "passive"))
      (node (ref "C30") (pin "2") (pinfunction "2_2") (pintype "passive"))
      (node (ref "C30A") (pin "2") (pinfunction "2_2") (pintype "passive"))
      (node (ref "C31") (pin "1") (pinfunction "1_1") (pintype "passive"))
      (node (ref "C31A") (pin "1") (pinfunction "1_1") (pintype "passive"))
      (node (ref "C32") (pin "2") (pinfunction "2_2") (pintype "passive"))
      (node (ref "C32A") (pin "2") (pinfunction "2_2") (pintype "passive"))
      (node (ref "C36") (pin "2") (pinfunction "2_2") (pintype "passive"))
      (node (ref "C36A") (pin "2") (pinfunction "2_2") (pintype "passive"))
      (node (ref "C37") (pin "+") (pinfunction "+_+") (pintype "passive"))
      (node (ref "C38") (pin "1") (pinfunction "1_1") (pintype "passive"))
      (node (ref "C38A") (pin "1") (pinfunction "1_1") (pintype "passive"))
      (node (ref "C4") (pin "2") (pinfunction "2_2") (pintype "passive"))
      (node (ref "C40") (pin "1") (pinfunction "1_1") (pintype "passive"))
      (node (ref "C40A") (pin "1") (pinfunction "1_1") (pintype "passive"))
      (node (ref "C41") (pin "2") (pinfunction "2_2") (pintype "passive"))
      (node (ref "C41A") (pin "2") (pinfunction "2_2") (pintype "passive"))
      (node (ref "C42") (pin "2") (pinfunction "2_2") (pintype "passive"))
      (node (ref "C42A") (pin "2") (pinfunction "2_2") (pintype "passive"))
      (node (ref "C43") (pin "2") (pinfunction "2_2") (pintype "passive"))
      (node (ref "C43A") (pin "2") (pinfunction "2_2") (pintype "passive"))
      (node (ref "C44") (pin "2") (pinfunction "2_2") (pintype "passive"))
      (node (ref "C44A") (pin "2") (pinfunction "2_2") (pintype "passive"))
      (node (ref "C45") (pin "2") (pinfunction "2_2") (pintype "passive"))
      (node (ref "C45A") (pin "2") (pinfunction "2_2") (pintype "passive"))
      (node (ref "C47") (pin "1") (pinfunction "1_1") (pintype "passive"))
      (node (ref "C47A") (pin "1") (pinfunction "1_1") (pintype "passive"))
      (node (ref "C48") (pin "2") (pinfunction "2_2") (pintype "passive"))
      (node (ref "C48A") (pin "2") (pinfunction "2_2") (pintype "passive"))
      (node (ref "C49") (pin "-") (pinfunction "-_-") (pintype "passive"))
      (node (ref "C4A") (pin "2") (pinfunction "2_2") (pintype "passive"))
      (node (ref "C5") (pin "2") (pinfunction "2_2") (pintype "passive"))
      (node (ref "C50") (pin "2") (pinfunction "2_2") (pintype "passive"))
      (node (ref "C50A") (pin "2") (pinfunction "2_2") (pintype "passive"))
      (node (ref "C51") (pin "2") (pinfunction "2_2") (pintype "passive"))
      (node (ref "C51A") (pin "2") (pinfunction "2_2") (pintype "passive"))
      (node (ref "C52") (pin "2") (pinfunction "2_2") (pintype "passive"))
      (node (ref "C52A") (pin "2") (pinfunction "2_2") (pintype "passive"))
      (node (ref "C53") (pin "1") (pinfunction "1_1") (pintype "passive"))
      (node (ref "C53A") (pin "1") (pinfunction "1_1") (pintype "passive"))
      (node (ref "C54") (pin "1") (pinfunction "1_1") (pintype "passive"))
      (node (ref "C54A") (pin "1") (pinfunction "1_1") (pintype "passive"))
      (node (ref "C57") (pin "2") (pinfunction "2_2") (pintype "passive"))
      (node (ref "C57A") (pin "2") (pinfunction "2_2") (pintype "passive"))
      (node (ref "C58") (pin "1") (pinfunction "1_1") (pintype "passive"))
      (node (ref "C58A") (pin "1") (pinfunction "1_1") (pintype "passive"))
      (node (ref "C5A") (pin "2") (pinfunction "2_2") (pintype "passive"))
      (node (ref "C6") (pin "2") (pinfunction "2_2") (pintype "passive"))
      (node (ref "C6A") (pin "2") (pinfunction "2_2") (pintype "passive"))
      (node (ref "C8") (pin "2") (pinfunction "2_2") (pintype "passive"))
      (node (ref "C8A") (pin "2") (pinfunction "2_2") (pintype "passive"))
      (node (ref "C9") (pin "2") (pinfunction "2_2") (pintype "passive"))
      (node (ref "C9A") (pin "2") (pinfunction "2_2") (pintype "passive"))
      (node (ref "IC1") (pin "3") (pinfunction "3_3") (pintype "passive"))
      (node (ref "IC10") (pin "3") (pinfunction "+IN_3") (pintype "input"))
      (node (ref "IC10") (pin "5") (pinfunction "+IN_5") (pintype "input"))
      (node (ref "IC11") (pin "13") (pinfunction "G_13") (pintype "input"))
      (node (ref "IC11") (pin "8") (pinfunction "GND_8") (pintype "power_in"))
      (node (ref "IC12") (pin "6") (pinfunction "INH_6") (pintype "input"))
      (node (ref "IC12") (pin "8") (pinfunction "GND_8") (pintype "power_in"))
      (node (ref "IC13") (pin "3") (pinfunction "Z1_3") (pintype "bidirectional"))
      (node (ref "IC13") (pin "6") (pinfunction "INH_6") (pintype "input"))
      (node (ref "IC13") (pin "8") (pinfunction "GND_8") (pintype "power_in"))
      (node (ref "IC14") (pin "2") (pinfunction "GND_2") (pintype "passive"))
      (node (ref "IC2") (pin "3") (pinfunction "+IN_3") (pintype "input"))
      (node (ref "IC2") (pin "5") (pinfunction "+IN_5") (pintype "input"))
      (node (ref "IC3") (pin "3") (pinfunction "+IN_3") (pintype "input"))
      (node (ref "IC3") (pin "5") (pinfunction "+IN_5") (pintype "input"))
      (node (ref "IC4") (pin "3") (pinfunction "+IN_3") (pintype "input"))
      (node (ref "IC4") (pin "5") (pinfunction "+IN_5") (pintype "input"))
      (node (ref "IC5") (pin "1") (pinfunction "GND_1") (pintype "passive"))
      (node (ref "IC6") (pin "3") (pinfunction "+IN_3") (pintype "input"))
      (node (ref "IC6") (pin "5") (pinfunction "+IN_5") (pintype "input"))
      (node (ref "IC7") (pin "8") (pinfunction "GND_8") (pintype "power_in"))
      (node (ref "IC9") (pin "8") (pinfunction "GND_8") (pintype "power_in"))
      (node (ref "J1") (pin "1") (pinfunction "1_1") (pintype "passive"))
      (node (ref "J2") (pin "S") (pinfunction "S_S") (pintype "passive"))
      (node (ref "J2") (pin "SN") (pinfunction "SN_SN") (pintype "passive"))
      (node (ref "J2") (pin "TN") (pinfunction "TN_TN") (pintype "passive"))
      (node (ref "J3") (pin "S") (pinfunction "S_S") (pintype "passive"))
      (node (ref "J3") (pin "SN") (pinfunction "SN_SN") (pintype "passive"))
      (node (ref "J5") (pin "1") (pinfunction "1_1") (pintype "passive"))
      (node (ref "J6") (pin "2") (pinfunction "2_2") (pintype "passive"))
      (node (ref "LED1") (pin "C") (pinfunction "C_C") (pintype "passive"))
      (node (ref "LED2") (pin "C") (pinfunction "C_C") (pintype "passive"))
      (node (ref "R1") (pin "A") (pinfunction "A_A") (pintype "passive"))
      (node (ref "R2") (pin "A") (pinfunction "A_A") (pintype "passive"))
      (node (ref "R28") (pin "1") (pinfunction "1_1") (pintype "passive"))
      (node (ref "R46") (pin "1") (pinfunction "1_1") (pintype "passive"))
    )
    (net (code "27") (name "Net-(C1-Pad+)") (class "Default")
      (node (ref "C1") (pin "+") (pinfunction "+_+") (pintype "passive"))
      (node (ref "R1") (pin "S") (pinfunction "S_S") (pintype "passive"))
    )
    (net (code "28") (name "Net-(C1-Pad-)") (class "Default")
      (node (ref "C1") (pin "-") (pinfunction "-_-") (pintype "passive"))
      (node (ref "R17") (pin "1") (pinfunction "1_1") (pintype "passive"))
    )
    (net (code "29") (name "Net-(C2-Pad+)") (class "Default")
      (node (ref "C2") (pin "+") (pinfunction "+_+") (pintype "passive"))
      (node (ref "C3") (pin "+") (pinfunction "+_+") (pintype "passive"))
      (node (ref "C7") (pin "1") (pinfunction "1_1") (pintype "passive"))
      (node (ref "C7A") (pin "1") (pinfunction "1_1") (pintype "passive"))
      (node (ref "IC1") (pin "2") (pinfunction "2_2") (pintype "passive"))
    )
    (net (code "30") (name "Net-(C2-Pad-)") (class "Default")
      (node (ref "C2") (pin "-") (pinfunction "-_-") (pintype "passive"))
      (node (ref "C3") (pin "-") (pinfunction "-_-") (pintype "passive"))
      (node (ref "IC1") (pin "4") (pinfunction "4_4") (pintype "passive"))
    )
    (net (code "31") (name "Net-(C7-Pad2)") (class "Default")
      (node (ref "C7") (pin "2") (pinfunction "2_2") (pintype "passive"))
      (node (ref "C7A") (pin "2") (pinfunction "2_2") (pintype "passive"))
      (node (ref "IC1") (pin "7") (pinfunction "7_7") (pintype "passive"))
    )
    (net (code "32") (name "Net-(C9-Pad1)") (class "Default")
      (node (ref "C9") (pin "1") (pinfunction "1_1") (pintype "passive"))
      (node (ref "C9A") (pin "1") (pinfunction "1_1") (pintype "passive"))
      (node (ref "R14") (pin "2") (pinfunction "2_2") (pintype "passive"))
      (node (ref "R9") (pin "1") (pinfunction "1_1") (pintype "passive"))
    )
    (net (code "33") (name "Net-(C20-Pad-)") (class "Default")
      (node (ref "C20") (pin "-") (pinfunction "-_-") (pintype "passive"))
      (node (ref "R31") (pin "1") (pinfunction "1_1") (pintype "passive"))
    )
    (net (code "34") (name "Net-(C21-Pad-)") (class "Default")
      (node (ref "C21") (pin "-") (pinfunction "-_-") (pintype "passive"))
      (node (ref "R32") (pin "1") (pinfunction "1_1") (pintype "passive"))
    )
    (net (code "35") (name "Net-(C24-Pad1)") (class "Default")
      (node (ref "C24") (pin "1") (pinfunction "1_1") (pintype "passive"))
      (node (ref "C24A") (pin "1") (pinfunction "1_1") (pintype "passive"))
      (node (ref "R22") (pin "1") (pinfunction "1_1") (pintype "passive"))
    )
    (net (code "36") (name "Net-(C25-Pad1)") (class "Default")
      (node (ref "C25") (pin "1") (pinfunction "1_1") (pintype "passive"))
      (node (ref "C25A") (pin "1") (pinfunction "1_1") (pintype "passive"))
      (node (ref "R23") (pin "1") (pinfunction "1_1") (pintype "passive"))
    )
    (net (code "37") (name "Net-(C29-Pad1)") (class "Default")
      (node (ref "C29") (pin "1") (pinfunction "1_1") (pintype "passive"))
      (node (ref "C29A") (pin "1") (pinfunction "1_1") (pintype "passive"))
      (node (ref "R33") (pin "1") (pinfunction "1_1") (pintype "passive"))
    )
    (net (code "38") (name "Net-(C30-Pad1)") (class "Default")
      (node (ref "C30") (pin "1") (pinfunction "1_1") (pintype "passive"))
      (node (ref "C30A") (pin "1") (pinfunction "1_1") (pintype "passive"))
      (node (ref "R34") (pin "1") (pinfunction "1_1") (pintype "passive"))
    )
    (net (code "39") (name "Net-(C34-Pad+)") (class "Default")
      (node (ref "C34") (pin "+") (pinfunction "+_+") (pintype "passive"))
      (node (ref "J4") (pin "1") (pinfunction "1_1") (pintype "passive"))
    )
    (net (code "40") (name "Net-(C34-Pad-)") (class "Default")
      (node (ref "C34") (pin "-") (pinfunction "-_-") (pintype "passive"))
      (node (ref "R20") (pin "1") (pinfunction "1_1") (pintype "passive"))
    )
    (net (code "41") (name "Net-(C41-Pad1)") (class "Default")
      (node (ref "C41") (pin "1") (pinfunction "1_1") (pintype "passive"))
      (node (ref "C41A") (pin "1") (pinfunction "1_1") (pintype "passive"))
      (node (ref "R38") (pin "1") (pinfunction "1_1") (pintype "passive"))
    )
    (net (code "42") (name "Net-(C42-Pad1)") (class "Default")
      (node (ref "C42") (pin "1") (pinfunction "1_1") (pintype "passive"))
      (node (ref "C42A") (pin "1") (pinfunction "1_1") (pintype "passive"))
      (node (ref "R39") (pin "1") (pinfunction "1_1") (pintype "passive"))
    )
    (net (code "43") (name "Net-(C44-Pad1)") (class "Default")
      (node (ref "C44") (pin "1") (pinfunction "1_1") (pintype "passive"))
      (node (ref "C44A") (pin "1") (pinfunction "1_1") (pintype "passive"))
      (node (ref "R48") (pin "1") (pinfunction "1_1") (pintype "passive"))
    )
    (net (code "44") (name "Net-(C45-Pad1)") (class "Default")
      (node (ref "C45") (pin "1") (pinfunction "1_1") (pintype "passive"))
      (node (ref "C45A") (pin "1") (pinfunction "1_1") (pintype "passive"))
      (node (ref "R49") (pin "1") (pinfunction "1_1") (pintype "passive"))
    )
    (net (code "45") (name "Net-(D1-PadA)") (class "Default")
      (node (ref "D1") (pin "A") (pinfunction "A_A") (pintype "passive"))
      (node (ref "D1A") (pin "A") (pinfunction "A_A") (pintype "passive"))
      (node (ref "SW") (pin "2") (pinfunction "2_2") (pintype "passive"))
    )
    (net (code "46") (name "Net-(D2-PadC)") (class "Default")
      (node (ref "D2") (pin "C") (pinfunction "C_C") (pintype "passive"))
      (node (ref "D3") (pin "C") (pinfunction "C_C") (pintype "passive"))
    )
    (net (code "47") (name "Net-(D4-PadC)") (class "Default")
      (node (ref "D4") (pin "C") (pinfunction "C_C") (pintype "passive"))
      (node (ref "D5") (pin "C") (pinfunction "C_C") (pintype "passive"))
    )
    (net (code "48") (name "Net-(IC2A--IN)") (class "Default")
      (node (ref "C13") (pin "1") (pinfunction "1_1") (pintype "passive"))
      (node (ref "C13A") (pin "1") (pinfunction "1_1") (pintype "passive"))
      (node (ref "IC2") (pin "2") (pinfunction "-IN_2") (pintype "input"))
      (node (ref "R13") (pin "1") (pinfunction "1_1") (pintype "passive"))
      (node (ref "R17") (pin "2") (pinfunction "2_2") (pintype "passive"))
      (node (ref "R20") (pin "2") (pinfunction "2_2") (pintype "passive"))
    )
    (net (code "49") (name "Net-(IC2B--IN)") (class "Default")
      (node (ref "C14") (pin "1") (pinfunction "1_1") (pintype "passive"))
      (node (ref "C14A") (pin "1") (pinfunction "1_1") (pintype "passive"))
      (node (ref "IC2") (pin "6") (pinfunction "-IN_6") (pintype "input"))
      (node (ref "IC9") (pin "13") (pinfunction "OUT_13") (pintype "output"))
      (node (ref "R12") (pin "2") (pinfunction "2_2") (pintype "passive"))
    )
    (net (code "50") (name "Net-(IC2B-OUT)") (class "Default")
      (node (ref "C14") (pin "2") (pinfunction "2_2") (pintype "passive"))
      (node (ref "C14A") (pin "2") (pinfunction "2_2") (pintype "passive"))
      (node (ref "IC2") (pin "7") (pinfunction "OUT_7") (pintype "output"))
      (node (ref "R12") (pin "1") (pinfunction "1_1") (pintype "passive"))
      (node (ref "R3") (pin "2") (pinfunction "2_2") (pintype "passive"))
    )
    (net (code "51") (name "Net-(IC3A--IN)") (class "Default")
      (node (ref "C10") (pin "1") (pinfunction "1_1") (pintype "passive"))
      (node (ref "C10A") (pin "1") (pinfunction "1_1") (pintype "passive"))
      (node (ref "IC3") (pin "2") (pinfunction "-IN_2") (pintype "input"))
      (node (ref "IC7") (pin "12") (pinfunction "OUT_12") (pintype "output"))
      (node (ref "R53") (pin "2") (pinfunction "2_2") (pintype "passive"))
      (node (ref "R9") (pin "2") (pinfunction "2_2") (pintype "passive"))
    )
    (net (code "52") (name "Net-(IC3A-OUT)") (class "Default")
      (node (ref "C10") (pin "2") (pinfunction "2_2") (pintype "passive"))
      (node (ref "C10A") (pin "2") (pinfunction "2_2") (pintype "passive"))
      (node (ref "IC3") (pin "1") (pinfunction "OUT_1") (pintype "output"))
      (node (ref "IC7") (pin "11") (pinfunction "CTRL_11") (pintype "input"))
      (node (ref "IC9") (pin "14") (pinfunction "CTRL_14") (pintype "input"))
    )
    (net (code "53") (name "Net-(IC3B--IN)") (class "Default")
      (node (ref "IC3") (pin "6") (pinfunction "-IN_6") (pintype "input"))
      (node (ref "IC3") (pin "7") (pinfunction "OUT_7") (pintype "output"))
    )
    (net (code "54") (name "Net-(IC4A--IN)") (class "Default")
      (node (ref "C11") (pin "1") (pinfunction "1_1") (pintype "passive"))
      (node (ref "C11A") (pin "1") (pinfunction "1_1") (pintype "passive"))
      (node (ref "IC4") (pin "2") (pinfunction "-IN_2") (pintype "input"))
      (node (ref "R10") (pin "1") (pinfunction "1_1") (pintype "passive"))
      (node (ref "R15") (pin "2") (pinfunction "2_2") (pintype "passive"))
      (node (ref "R18") (pin "2") (pinfunction "2_2") (pintype "passive"))
    )
    (net (code "55") (name "Net-(IC4B--IN)") (class "Default")
      (node (ref "C12") (pin "1") (pinfunction "1_1") (pintype "passive"))
      (node (ref "C12A") (pin "1") (pinfunction "1_1") (pintype "passive"))
      (node (ref "IC4") (pin "6") (pinfunction "-IN_6") (pintype "input"))
      (node (ref "R11") (pin "1") (pinfunction "1_1") (pintype "passive"))
      (node (ref "R16") (pin "2") (pinfunction "2_2") (pintype "passive"))
      (node (ref "R19") (pin "2") (pinfunction "2_2") (pintype "passive"))
    )
    (net (code "56") (name "Net-(IC5-VI)") (class "Default")
      (node (ref "C15") (pin "-") (pinfunction "-_-") (pintype "passive"))
      (node (ref "C58") (pin "2") (pinfunction "2_2") (pintype "passive"))
      (node (ref "C58A") (pin "2") (pinfunction "2_2") (pintype "passive"))
      (node (ref "IC1") (pin "5") (pinfunction "5_5") (pintype "passive"))
      (node (ref "IC5") (pin "2") (pinfunction "VI_2") (pintype "input"))
    )
    (net (code "57") (name "Net-(IC6A--IN)") (class "Default")
      (node (ref "C39") (pin "1") (pinfunction "1_1") (pintype "passive"))
      (node (ref "D5") (pin "A") (pinfunction "A_A") (pintype "passive"))
      (node (ref "IC6") (pin "2") (pinfunction "-IN_2") (pintype "input"))
      (node (ref "IC7") (pin "4") (pinfunction "OUT_4") (pintype "output"))
      (node (ref "R44") (pin "2") (pinfunction "2_2") (pintype "passive"))
    )
    (net (code "58") (name "Net-(IC6B--IN)") (class "Default")
      (node (ref "C35") (pin "1") (pinfunction "1_1") (pintype "passive"))
      (node (ref "IC6") (pin "6") (pinfunction "-IN_6") (pintype "input"))
      (node (ref "IC7") (pin "13") (pinfunction "OUT_13") (pintype "output"))
      (node (ref "R55") (pin "2") (pinfunction "2_2") (pintype "passive"))
    )
    (net (code "59") (name "Net-(IC7A-IN)") (class "Default")
      (node (ref "IC7") (pin "2") (pinfunction "IN_2") (pintype "input"))
      (node (ref "R37") (pin "2") (pinfunction "2_2") (pintype "passive"))
      (node (ref "R38") (pin "2") (pinfunction "2_2") (pintype "passive"))
    )
    (net (code "60") (name "Net-(IC7B-IN)") (class "Default")
      (node (ref "IC7") (pin "7") (pinfunction "IN_7") (pintype "input"))
      (node (ref "R39") (pin "2") (pinfunction "2_2") (pintype "passive"))
      (node (ref "R40") (pin "1") (pinfunction "1_1") (pintype "passive"))
    )
    (net (code "61") (name "Net-(IC7B-OUT)") (class "Default")
      (node (ref "C55") (pin "1") (pinfunction "1_1") (pintype "passive"))
      (node (ref "C55A") (pin "1") (pinfunction "1_1") (pintype "passive"))
      (node (ref "IC7") (pin "5") (pinfunction "OUT_5") (pintype "output"))
      (node (ref "IC8") (pin "3") (pinfunction "+IN_3") (pintype "input"))
      (node (ref "R42") (pin "2") (pinfunction "2_2") (pintype "passive"))
      (node (ref "R46") (pin "2") (pinfunction "2_2") (pintype "passive"))
      (node (ref "R54") (pin "1") (pinfunction "1_1") (pintype "passive"))
    )
    (net (code "62") (name "Net-(IC7C-IN)") (class "Default")
      (node (ref "IC7") (pin "10") (pinfunction "IN_10") (pintype "input"))
      (node (ref "R23") (pin "2") (pinfunction "2_2") (pintype "passive"))
      (node (ref "R24") (pin "1") (pinfunction "1_1") (pintype "passive"))
    )
    (net (code "63") (name "Net-(IC7D-IN)") (class "Default")
      (node (ref "IC7") (pin "15") (pinfunction "IN_15") (pintype "input"))
      (node (ref "R22") (pin "2") (pinfunction "2_2") (pintype "passive"))
      (node (ref "R36") (pin "2") (pinfunction "2_2") (pintype "passive"))
    )
    (net (code "64") (name "Net-(IC8A--IN)") (class "Default")
      (node (ref "IC8") (pin "2") (pinfunction "-IN_2") (pintype "input"))
      (node (ref "R41") (pin "1") (pinfunction "1_1") (pintype "passive"))
      (node (ref "R43") (pin "1") (pinfunction "1_1") (pintype "passive"))
      (node (ref "R45") (pin "2") (pinfunction "2_2") (pintype "passive"))
    )
    (net (code "65") (name "Net-(IC8B-+IN)") (class "Default")
      (node (ref "C56") (pin "1") (pinfunction "1_1") (pintype "passive"))
      (node (ref "C56A") (pin "1") (pinfunction "1_1") (pintype "passive"))
      (node (ref "IC8") (pin "5") (pinfunction "+IN_5") (pintype "input"))
      (node (ref "IC9") (pin "4") (pinfunction "OUT_4") (pintype "output"))
      (node (ref "R27") (pin "2") (pinfunction "2_2") (pintype "passive"))
      (node (ref "R28") (pin "2") (pinfunction "2_2") (pintype "passive"))
      (node (ref "R30") (pin "1") (pinfunction "1_1") (pintype "passive"))
    )
    (net (code "66") (name "Net-(IC8B--IN)") (class "Default")
      (node (ref "IC8") (pin "6") (pinfunction "-IN_6") (pintype "input"))
      (node (ref "R25") (pin "1") (pinfunction "1_1") (pintype "passive"))
      (node (ref "R26") (pin "1") (pinfunction "1_1") (pintype "passive"))
      (node (ref "R29") (pin "2") (pinfunction "2_2") (pintype "passive"))
    )
    (net (code "67") (name "Net-(IC9A-IN)") (class "Default")
      (node (ref "IC9") (pin "2") (pinfunction "IN_2") (pintype "input"))
      (node (ref "R47") (pin "1") (pinfunction "1_1") (pintype "passive"))
      (node (ref "R48") (pin "2") (pinfunction "2_2") (pintype "passive"))
    )
    (net (code "68") (name "Net-(IC9B-IN)") (class "Default")
      (node (ref "IC9") (pin "7") (pinfunction "IN_7") (pintype "input"))
      (node (ref "R49") (pin "2") (pinfunction "2_2") (pintype "passive"))
      (node (ref "R50") (pin "2") (pinfunction "2_2") (pintype "passive"))
    )
    (net (code "69") (name "Net-(IC9C-IN)") (class "Default")
      (node (ref "IC9") (pin "10") (pinfunction "IN_10") (pintype "input"))
      (node (ref "R34") (pin "2") (pinfunction "2_2") (pintype "passive"))
      (node (ref "R35") (pin "2") (pinfunction "2_2") (pintype "passive"))
    )
    (net (code "70") (name "Net-(IC9D-IN)") (class "Default")
      (node (ref "IC9") (pin "15") (pinfunction "IN_15") (pintype "input"))
      (node (ref "R31") (pin "2") (pinfunction "2_2") (pintype "passive"))
      (node (ref "R32") (pin "2") (pinfunction "2_2") (pintype "passive"))
      (node (ref "R33") (pin "2") (pinfunction "2_2") (pintype "passive"))
    )
    (net (code "71") (name "Net-(IC10A--IN)") (class "Default")
      (node (ref "C46") (pin "1") (pinfunction "1_1") (pintype "passive"))
      (node (ref "IC10") (pin "2") (pinfunction "-IN_2") (pintype "input"))
      (node (ref "IC9") (pin "5") (pinfunction "OUT_5") (pintype "output"))
      (node (ref "R57") (pin "2") (pinfunction "2_2") (pintype "passive"))
    )
    (net (code "72") (name "Net-(IC10B--IN)") (class "Default")
      (node (ref "C33") (pin "1") (pinfunction "1_1") (pintype "passive"))
      (node (ref "D3") (pin "A") (pinfunction "A_A") (pintype "passive"))
      (node (ref "IC10") (pin "6") (pinfunction "-IN_6") (pintype "input"))
      (node (ref "IC9") (pin "12") (pinfunction "OUT_12") (pintype "output"))
      (node (ref "R56") (pin "2") (pinfunction "2_2") (pintype "passive"))
    )
    (net (code "73") (name "Net-(IC11A-QG)") (class "Default")
      (node (ref "IC11") (pin "6") (pinfunction "QG_6") (pintype "tri_state"))
      (node (ref "R51") (pin "2") (pinfunction "2_2") (pintype "passive"))
    )
    (net (code "74") (name "Net-(IC11A-QH)") (class "Default")
      (node (ref "IC11") (pin "7") (pinfunction "QH_7") (pintype "tri_state"))
      (node (ref "R52") (pin "2") (pinfunction "2_2") (pintype "passive"))
    )
    (net (code "75") (name "Net-(IC11A-RCK)") (class "Default")
      (node (ref "IC11") (pin "12") (pinfunction "RCK_12") (pintype "input"))
      (node (ref "J6") (pin "5") (pinfunction "5_5") (pintype "passive"))
    )
    (net (code "76") (name "Net-(IC11A-SCK)") (class "Default")
      (node (ref "IC11") (pin "11") (pinfunction "SCK_11") (pintype "input"))
      (node (ref "J6") (pin "4") (pinfunction "4_4") (pintype "passive"))
    )
    (net (code "77") (name "Net-(IC11A-SER)") (class "Default")
      (node (ref "IC11") (pin "14") (pinfunction "SER_14") (pintype "input"))
      (node (ref "J6") (pin "3") (pinfunction "3_3") (pintype "passive"))
    )
    (net (code "78") (name "Net-(IC12A-X)") (class "Default")
      (node (ref "IC12") (pin "14") (pinfunction "X_14") (pintype "bidirectional"))
      (node (ref "IC12") (pin "2") (pinfunction "Y0_2") (pintype "bidirectional"))
    )
    (net (code "79") (name "Net-(IC12A-Z)") (class "Default")
      (node (ref "IC12") (pin "4") (pinfunction "Z_4") (pintype "bidirectional"))
      (node (ref "R27") (pin "1") (pinfunction "1_1") (pintype "passive"))
    )
    (net (code "80") (name "Net-(IC13A-X)") (class "Default")
      (node (ref "IC13") (pin "14") (pinfunction "X_14") (pintype "bidirectional"))
      (node (ref "IC13") (pin "2") (pinfunction "Y0_2") (pintype "bidirectional"))
    )
    (net (code "81") (name "Net-(IC14-VI)") (class "Default")
      (node (ref "C16") (pin "+") (pinfunction "+_+") (pintype "passive"))
      (node (ref "C57") (pin "1") (pinfunction "1_1") (pintype "passive"))
      (node (ref "C57A") (pin "1") (pinfunction "1_1") (pintype "passive"))
      (node (ref "D1") (pin "C") (pinfunction "C_C") (pintype "passive"))
      (node (ref "D1A") (pin "C") (pinfunction "C_C") (pintype "passive"))
      (node (ref "IC1") (pin "8") (pinfunction "8_8") (pintype "passive"))
      (node (ref "IC14") (pin "1") (pinfunction "VI_1") (pintype "input"))
    )
    (net (code "82") (name "Net-(J1-Pad3)") (class "Default")
      (node (ref "J1") (pin "3") (pinfunction "3_3") (pintype "passive"))
      (node (ref "SW") (pin "1") (pinfunction "1_1") (pintype "passive"))
    )
    (net (code "83") (name "Net-(J2-PadT)") (class "Default")
      (node (ref "J2") (pin "T") (pinfunction "T_T") (pintype "passive"))
      (node (ref "R1") (pin "E") (pinfunction "E_E") (pintype "passive"))
    )
    (net (code "84") (name "Net-(J3-PadT)") (class "Default")
      (node (ref "J3") (pin "T") (pinfunction "T_T") (pintype "passive"))
      (node (ref "R2") (pin "S") (pinfunction "S_S") (pintype "passive"))
    )
    (net (code "85") (name "Net-(J4-Pad2)") (class "Default")
      (node (ref "J4") (pin "2") (pinfunction "2_2") (pintype "passive"))
      (node (ref "R14") (pin "1") (pinfunction "1_1") (pintype "passive"))
    )
    (net (code "86") (name "Net-(J4-Pad4)") (class "Default")
      (node (ref "J4") (pin "4") (pinfunction "4_4") (pintype "passive"))
      (node (ref "R21") (pin "1") (pinfunction "1_1") (pintype "passive"))
    )
    (net (code "87") (name "Net-(J4-Pad5)") (class "Default")
      (node (ref "J4") (pin "5") (pinfunction "5_5") (pintype "passive"))
      (node (ref "R8") (pin "1") (pinfunction "1_1") (pintype "passive"))
    )
    (net (code "88") (name "Net-(LED1-PadA)") (class "Default")
      (node (ref "LED1") (pin "A") (pinfunction "A_A") (pintype "passive"))
      (node (ref "R51") (pin "1") (pinfunction "1_1") (pintype "passive"))
    )
    (net (code "89") (name "Net-(LED2-PadA)") (class "Default")
      (node (ref "LED2") (pin "A") (pinfunction "A_A") (pintype "passive"))
      (node (ref "R52") (pin "1") (pinfunction "1_1") (pintype "passive"))
    )
    (net (code "90") (name "Net-(R2-PadE)") (class "Default")
      (node (ref "R2") (pin "E") (pinfunction "E_E") (pintype "passive"))
      (node (ref "R3") (pin "1") (pinfunction "1_1") (pintype "passive"))
    )
    (net (code "91") (name "Net-(R4-E)") (class "Default")
      (node (ref "R15") (pin "1") (pinfunction "1_1") (pintype "passive"))
      (node (ref "R4") (pin "1") (pinfunction "E_1") (pintype "passive"))
      (node (ref "R4") (pin "2") (pinfunction "S_2") (pintype "passive"))
    )
    (net (code "92") (name "Net-(R5-A)") (class "Default")
      (node (ref "J4") (pin "3") (pinfunction "3_3") (pintype "passive"))
      (node (ref "R5") (pin "3") (pinfunction "A_3") (pintype "passive"))
    )
    (net (code "93") (name "Net-(R5-E)") (class "Default")
      (node (ref "R18") (pin "1") (pinfunction "1_1") (pintype "passive"))
      (node (ref "R5") (pin "1") (pinfunction "E_1") (pintype "passive"))
      (node (ref "R5") (pin "2") (pinfunction "S_2") (pintype "passive"))
    )
    (net (code "94") (name "Net-(R6-A)") (class "Default")
      (node (ref "J4") (pin "6") (pinfunction "6_6") (pintype "passive"))
      (node (ref "R6") (pin "3") (pinfunction "A_3") (pintype "passive"))
    )
    (net (code "95") (name "Net-(R6-E)") (class "Default")
      (node (ref "R19") (pin "1") (pinfunction "1_1") (pintype "passive"))
      (node (ref "R6") (pin "1") (pinfunction "E_1") (pintype "passive"))
      (node (ref "R6") (pin "2") (pinfunction "S_2") (pintype "passive"))
    )
    (net (code "96") (name "Net-(R7-E)") (class "Default")
      (node (ref "R16") (pin "1") (pinfunction "1_1") (pintype "passive"))
      (node (ref "R7") (pin "1") (pinfunction "E_1") (pintype "passive"))
      (node (ref "R7") (pin "2") (pinfunction "S_2") (pintype "passive"))
    )
    (net (code "97") (name "VCC") (class "Default")
      (node (ref "C23") (pin "1") (pinfunction "1_1") (pintype "passive"))
      (node (ref "C23A") (pin "1") (pinfunction "1_1") (pintype "passive"))
      (node (ref "C28") (pin "1") (pinfunction "1_1") (pintype "passive"))
      (node (ref "C28A") (pin "1") (pinfunction "1_1") (pintype "passive"))
      (node (ref "C32") (pin "1") (pinfunction "1_1") (pintype "passive"))
      (node (ref "C32A") (pin "1") (pinfunction "1_1") (pintype "passive"))
      (node (ref "C36") (pin "1") (pinfunction "1_1") (pintype "passive"))
      (node (ref "C36A") (pin "1") (pinfunction "1_1") (pintype "passive"))
      (node (ref "C4") (pin "1") (pinfunction "1_1") (pintype "passive"))
      (node (ref "C43") (pin "1") (pinfunction "1_1") (pintype "passive"))
      (node (ref "C43A") (pin "1") (pinfunction "1_1") (pintype "passive"))
      (node (ref "C48") (pin "1") (pinfunction "1_1") (pintype "passive"))
      (node (ref "C48A") (pin "1") (pinfunction "1_1") (pintype "passive"))
      (node (ref "C49") (pin "+") (pinfunction "+_+") (pintype "passive"))
      (node (ref "C4A") (pin "1") (pinfunction "1_1") (pintype "passive"))
      (node (ref "C5") (pin "1") (pinfunction "1_1") (pintype "passive"))
      (node (ref "C50") (pin "1") (pinfunction "1_1") (pintype "passive"))
      (node (ref "C50A") (pin "1") (pinfunction "1_1") (pintype "passive"))
      (node (ref "C51") (pin "1") (pinfunction "1_1") (pintype "passive"))
      (node (ref "C51A") (pin "1") (pinfunction "1_1") (pintype "passive"))
      (node (ref "C52") (pin "1") (pinfunction "1_1") (pintype "passive"))
      (node (ref "C52A") (pin "1") (pinfunction "1_1") (pintype "passive"))
      (node (ref "C5A") (pin "1") (pinfunction "1_1") (pintype "passive"))
      (node (ref "C6") (pin "1") (pinfunction "1_1") (pintype "passive"))
      (node (ref "C6A") (pin "1") (pinfunction "1_1") (pintype "passive"))
      (node (ref "IC10") (pin "8") (pinfunction "V+_8") (pintype "power_in"))
      (node (ref "IC11") (pin "10") (pinfunction "SCL_10") (pintype "input"))
      (node (ref "IC11") (pin "16") (pinfunction "VCC_16") (pintype "power_in"))
      (node (ref "IC12") (pin "16") (pinfunction "VCC_16") (pintype "power_in"))
      (node (ref "IC13") (pin "16") (pinfunction "VCC_16") (pintype "power_in"))
      (node (ref "IC14") (pin "3") (pinfunction "VO_3") (pintype "passive"))
      (node (ref "IC2") (pin "8") (pinfunction "V+_8") (pintype "power_in"))
      (node (ref "IC3") (pin "8") (pinfunction "V+_8") (pintype "power_in"))
      (node (ref "IC4") (pin "8") (pinfunction "V+_8") (pintype "power_in"))
      (node (ref "IC6") (pin "8") (pinfunction "V+_8") (pintype "power_in"))
      (node (ref "IC7") (pin "16") (pinfunction "V+_16") (pintype "power_in"))
      (node (ref "IC8") (pin "8") (pinfunction "V+_8") (pintype "power_in"))
      (node (ref "IC9") (pin "16") (pinfunction "V+_16") (pintype "power_in"))
      (node (ref "J5") (pin "2") (pinfunction "2_2") (pintype "passive"))
    )
    (net (code "98") (name "VEE") (class "Default")
      (node (ref "C17") (pin "2") (pinfunction "2_2") (pintype "passive"))
      (node (ref "C17A") (pin "2") (pinfunction "2_2") (pintype "passive"))
      (node (ref "C18") (pin "2") (pinfunction "2_2") (pintype "passive"))
      (node (ref "C18A") (pin "2") (pinfunction "2_2") (pintype "passive"))
      (node (ref "C19") (pin "2") (pinfunction "2_2") (pintype "passive"))
      (node (ref "C19A") (pin "2") (pinfunction "2_2") (pintype "passive"))
      (node (ref "C26") (pin "2") (pinfunction "2_2") (pintype "passive"))
      (node (ref "C26A") (pin "2") (pinfunction "2_2") (pintype "passive"))
      (node (ref "C27") (pin "2") (pinfunction "2_2") (pintype "passive"))
      (node (ref "C27A") (pin "2") (pinfunction "2_2") (pintype "passive"))
      (node (ref "C31") (pin "2") (pinfunction "2_2") (pintype "passive"))
      (node (ref "C31A") (pin "2") (pinfunction "2_2") (pintype "passive"))
      (node (ref "C37") (pin "-") (pinfunction "-_-") (pintype "passive"))
      (node (ref "C38") (pin "2") (pinfunction "2_2") (pintype "passive"))
      (node (ref "C38A") (pin "2") (pinfunction "2_2") (pintype "passive"))
      (node (ref "C40") (pin "2") (pinfunction "2_2") (pintype "passive"))
      (node (ref "C40A") (pin "2") (pinfunction "2_2") (pintype "passive"))
      (node (ref "C47") (pin "2") (pinfunction "2_2") (pintype "passive"))
      (node (ref "C47A") (pin "2") (pinfunction "2_2") (pintype "passive"))
      (node (ref "C53") (pin "2") (pinfunction "2_2") (pintype "passive"))
      (node (ref "C53A") (pin "2") (pinfunction "2_2") (pintype "passive"))
      (node (ref "C54") (pin "2") (pinfunction "2_2") (pintype "passive"))
      (node (ref "C54A") (pin "2") (pinfunction "2_2") (pintype "passive"))
      (node (ref "IC10") (pin "4") (pinfunction "V-_4") (pintype "power_in"))
      (node (ref "IC12") (pin "7") (pinfunction "VEE_7") (pintype "power_in"))
      (node (ref "IC13") (pin "7") (pinfunction "VEE_7") (pintype "power_in"))
      (node (ref "IC2") (pin "4") (pinfunction "V-_4") (pintype "power_in"))
      (node (ref "IC3") (pin "4") (pinfunction "V-_4") (pintype "power_in"))
      (node (ref "IC4") (pin "4") (pinfunction "V-_4") (pintype "power_in"))
      (node (ref "IC5") (pin "3") (pinfunction "VO_3") (pintype "passive"))
      (node (ref "IC6") (pin "4") (pinfunction "V-_4") (pintype "power_in"))
      (node (ref "IC7") (pin "9") (pinfunction "V-_9") (pintype "power_in"))
      (node (ref "IC8") (pin "4") (pinfunction "V-_4") (pintype "power_in"))
      (node (ref "IC9") (pin "9") (pinfunction "V-_9") (pintype "power_in"))
      (node (ref "R24") (pin "2") (pinfunction "2_2") (pintype "passive"))
      (node (ref "R4") (pin "3") (pinfunction "A_3") (pintype "passive"))
      (node (ref "R53") (pin "1") (pinfunction "1_1") (pintype "passive"))
      (node (ref "R7") (pin "3") (pinfunction "A_3") (pintype "passive"))
    )
    (net (code "99") (name "unconnected-(IC1-Pad1)") (class "Default")
      (node (ref "IC1") (pin "1") (pinfunction "1_1") (pintype "passive"))
    )
    (net (code "100") (name "unconnected-(IC1-Pad6)") (class "Default")
      (node (ref "IC1") (pin "6") (pinfunction "6_6") (pintype "passive"))
    )
    (net (code "101") (name "unconnected-(IC7E-MODE-Pad1)") (class "Default")
      (node (ref "IC7") (pin "1") (pinfunction "MODE_1") (pintype "input"))
    )
    (net (code "102") (name "unconnected-(IC9E-MODE-Pad1)") (class "Default")
      (node (ref "IC9") (pin "1") (pinfunction "MODE_1") (pintype "input"))
    )
    (net (code "103") (name "unconnected-(IC11A-QH*-Pad9)") (class "Default")
      (node (ref "IC11") (pin "9") (pinfunction "QH*_9") (pintype "tri_state"))
    )
    (net (code "104") (name "unconnected-(J1-Pad2)") (class "Default")
      (node (ref "J1") (pin "2") (pinfunction "2_2") (pintype "passive"))
    )
    (net (code "105") (name "unconnected-(J3-PadTN)") (class "Default")
      (node (ref "J3") (pin "TN") (pinfunction "TN_TN") (pintype "passive"))
    )
    (net (code "106") (name "unconnected-(J6-Pad1)") (class "Default")
      (node (ref "J6") (pin "1") (pinfunction "1_1") (pintype "passive"))
    )
    (net (code "107") (name "unconnected-(J6-Pad6)") (class "Default")
      (node (ref "J6") (pin "6") (pinfunction "6_6") (pintype "passive"))
    )
  )
)
